# altimetrModul.net
KiCad netlist of a schematic drawn in EAGLE
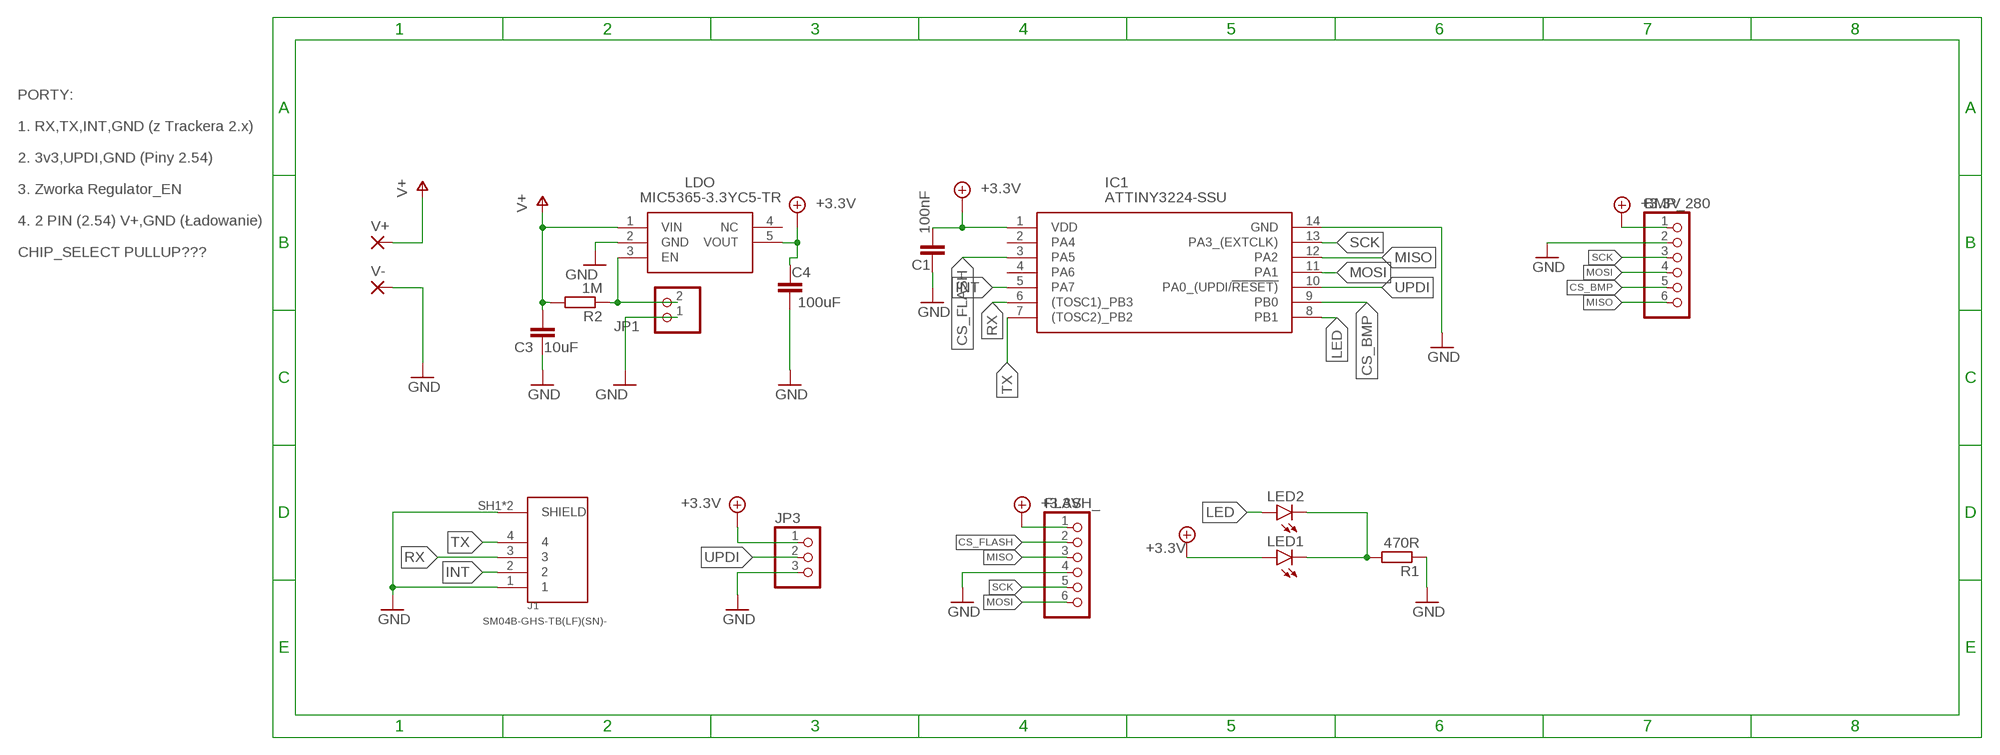
[diagram p0: schematic, sheet 1]

(export (version "E")
  (design (tool "Eeschema 10.0.6"))
  (components
    (comp (ref "BMP_280")
      (value "PINHD-1X6")
      (footprint "eagle-import:1X06")
      (libsource (lib "eagle-import") (part "PINHD-1X6"))
    )
    (comp (ref "C1")
      (value "100nF")
      (footprint "eagle-import:C0805")
      (libsource (lib "eagle-import") (part "C-EUC0805"))
    )
    (comp (ref "C3")
      (value "10uF")
      (footprint "eagle-import:C0805")
      (libsource (lib "eagle-import") (part "C-EUC0805"))
    )
    (comp (ref "C4")
      (value "100uF")
      (footprint "eagle-import:C0805")
      (libsource (lib "eagle-import") (part "C-EUC0805"))
    )
    (comp (ref "FLASH_")
      (value "PINHD-1X6")
      (footprint "eagle-import:1X06")
      (libsource (lib "eagle-import") (part "PINHD-1X6"))
    )
    (comp (ref "IC1")
      (value "ATTINY3224-SSU")
      (footprint "eagle-import:SOIC127P600X175-14N")
      (fields (field (name "MOUSER_PART_NUMBER") "579-ATTINY3224-SSU"))
      (libsource (lib "eagle-import") (part "ATTINY3224-SSU"))
    )
    (comp (ref "J1")
      (value "SM04B-GHS-TB(LF)(SN)-")
      (footprint "eagle-import:JST_SM04B-GHS-TB(LF)(SN)-")
      (fields (field (name "DIGI-KEY_PART_NUMBER") "455-1566-6-ND") (field (name "MF") "JST Sales"))
      (libsource (lib "eagle-import") (part "SM04B-GHS-TB(LF)(SN)-"))
    )
    (comp (ref "JP1")
      (value "PINHD-1X2/90")
      (footprint "eagle-import:1X02_90")
      (libsource (lib "eagle-import") (part "PINHD-1X2/90"))
    )
    (comp (ref "JP3")
      (value "PINHD-1X3/90")
      (footprint "eagle-import:1X03_90")
      (libsource (lib "eagle-import") (part "PINHD-1X3/90"))
    )
    (comp (ref "LDO")
      (value "MIC5365-3.3YC5-TR")
      (footprint "eagle-import:SOT65P210X110-5N")
      (fields (field (name "MOUSER_PART_NUMBER") "998-MIC5365-3.3YC5TR"))
      (libsource (lib "eagle-import") (part "MIC5365-3.3YC5-TR"))
    )
    (comp (ref "LED1")
      (value "LEDCHIP-LED0805")
      (footprint "eagle-import:CHIP-LED0805")
      (libsource (lib "eagle-import") (part "LEDCHIP-LED0805"))
    )
    (comp (ref "LED2")
      (value "LEDCHIP-LED0805")
      (footprint "eagle-import:CHIP-LED0805")
      (libsource (lib "eagle-import") (part "LEDCHIP-LED0805"))
    )
    (comp (ref "R1")
      (value "470R")
      (footprint "eagle-import:R0805")
      (libsource (lib "eagle-import") (part "rcl_334_R-EU_R0805"))
    )
    (comp (ref "R2")
      (value "1M")
      (footprint "eagle-import:R0805")
      (libsource (lib "eagle-import") (part "R-EU_R0805"))
    )
    (comp (ref "V+")
      (value "SMD2")
      (footprint "eagle-import:SMD1,27-2,54")
      (libsource (lib "eagle-import") (part "SMD2"))
    )
    (comp (ref "V-")
      (value "SMD2")
      (footprint "eagle-import:SMD1,27-2,54")
      (libsource (lib "eagle-import") (part "SMD2"))
    )
  )
  (nets
    (net (code "1") (name "+3.3V") (class "Default")
      (node (ref "BMP_280") (pin "1") (pinfunction "1_1") (pintype "passive"))
      (node (ref "C1") (pin "1") (pinfunction "1_1") (pintype "passive"))
      (node (ref "C4") (pin "2") (pinfunction "2_2") (pintype "passive"))
      (node (ref "FLASH_") (pin "1") (pinfunction "1_1") (pintype "passive"))
      (node (ref "IC1") (pin "1") (pinfunction "VDD_1") (pintype "bidirectional"))
      (node (ref "JP3") (pin "1") (pinfunction "1_1") (pintype "passive"))
      (node (ref "LDO") (pin "5") (pinfunction "VOUT_5") (pintype "output"))
      (node (ref "LED1") (pin "A") (pinfunction "A_A") (pintype "passive"))
    )
    (net (code "2") (name "CS_BMP") (class "Default")
      (node (ref "BMP_280") (pin "5") (pinfunction "5_5") (pintype "passive"))
      (node (ref "IC1") (pin "9") (pinfunction "PB0_9") (pintype "bidirectional"))
    )
    (net (code "3") (name "CS_FLASH") (class "Default")
      (node (ref "FLASH_") (pin "2") (pinfunction "2_2") (pintype "passive"))
      (node (ref "IC1") (pin "3") (pinfunction "PA5_3") (pintype "bidirectional"))
    )
    (net (code "4") (name "GND") (class "Default")
      (node (ref "BMP_280") (pin "2") (pinfunction "2_2") (pintype "passive"))
      (node (ref "C1") (pin "2") (pinfunction "2_2") (pintype "passive"))
      (node (ref "C3") (pin "1") (pinfunction "1_1") (pintype "passive"))
      (node (ref "C4") (pin "1") (pinfunction "1_1") (pintype "passive"))
      (node (ref "FLASH_") (pin "4") (pinfunction "4_4") (pintype "passive"))
      (node (ref "IC1") (pin "14") (pinfunction "GND_14") (pintype "bidirectional"))
      (node (ref "J1") (pin "1") (pinfunction "1_1") (pintype "passive"))
      (node (ref "J1") (pin "SH1") (pinfunction "SHIELD_SH1") (pintype "power_in"))
      (node (ref "J1") (pin "SH2") (pinfunction "SHIELD_SH2") (pintype "power_in"))
      (node (ref "JP1") (pin "1") (pinfunction "1_1") (pintype "passive"))
      (node (ref "JP3") (pin "3") (pinfunction "3_3") (pintype "passive"))
      (node (ref "LDO") (pin "2") (pinfunction "GND_2") (pintype "power_in"))
      (node (ref "R1") (pin "1") (pinfunction "1_1") (pintype "passive"))
      (node (ref "V-") (pin "1") (pinfunction "P_1") (pintype "passive"))
    )
    (net (code "5") (name "INT") (class "Default")
      (node (ref "IC1") (pin "5") (pinfunction "PA7_5") (pintype "bidirectional"))
      (node (ref "J1") (pin "2") (pinfunction "2_2") (pintype "passive"))
    )
    (net (code "6") (name "LED") (class "Default")
      (node (ref "IC1") (pin "8") (pinfunction "PB1_8") (pintype "bidirectional"))
      (node (ref "LED2") (pin "A") (pinfunction "A_A") (pintype "passive"))
    )
    (net (code "7") (name "MISO") (class "Default")
      (node (ref "BMP_280") (pin "6") (pinfunction "6_6") (pintype "passive"))
      (node (ref "FLASH_") (pin "3") (pinfunction "3_3") (pintype "passive"))
      (node (ref "IC1") (pin "12") (pinfunction "PA2_12") (pintype "bidirectional"))
    )
    (net (code "8") (name "MOSI") (class "Default")
      (node (ref "BMP_280") (pin "4") (pinfunction "4_4") (pintype "passive"))
      (node (ref "FLASH_") (pin "6") (pinfunction "6_6") (pintype "passive"))
      (node (ref "IC1") (pin "11") (pinfunction "PA1_11") (pintype "bidirectional"))
    )
    (net (code "9") (name "Net-(LDO-EN)") (class "Default")
      (node (ref "JP1") (pin "2") (pinfunction "2_2") (pintype "passive"))
      (node (ref "LDO") (pin "3") (pinfunction "EN_3") (pintype "input"))
      (node (ref "R2") (pin "1") (pinfunction "1_1") (pintype "passive"))
    )
    (net (code "10") (name "Net-(LED1-PadC)") (class "Default")
      (node (ref "LED1") (pin "C") (pinfunction "C_C") (pintype "passive"))
      (node (ref "LED2") (pin "C") (pinfunction "C_C") (pintype "passive"))
      (node (ref "R1") (pin "2") (pinfunction "2_2") (pintype "passive"))
    )
    (net (code "11") (name "RX") (class "Default")
      (node (ref "IC1") (pin "6") (pinfunction "(TOSC1)_PB3_6") (pintype "bidirectional"))
      (node (ref "J1") (pin "3") (pinfunction "3_3") (pintype "passive"))
    )
    (net (code "12") (name "SCK") (class "Default")
      (node (ref "BMP_280") (pin "3") (pinfunction "3_3") (pintype "passive"))
      (node (ref "FLASH_") (pin "5") (pinfunction "5_5") (pintype "passive"))
      (node (ref "IC1") (pin "13") (pinfunction "PA3_(EXTCLK)_13") (pintype "bidirectional"))
    )
    (net (code "13") (name "TX") (class "Default")
      (node (ref "IC1") (pin "7") (pinfunction "(TOSC2)_PB2_7") (pintype "bidirectional"))
      (node (ref "J1") (pin "4") (pinfunction "4_4") (pintype "passive"))
    )
    (net (code "14") (name "UPDI") (class "Default")
      (node (ref "IC1") (pin "10") (pinfunction "PA0_(UPDI/~{RESET})_10") (pintype "bidirectional"))
      (node (ref "JP3") (pin "2") (pinfunction "2_2") (pintype "passive"))
    )
    (net (code "15") (name "V+") (class "Default")
      (node (ref "C3") (pin "2") (pinfunction "2_2") (pintype "passive"))
      (node (ref "LDO") (pin "1") (pinfunction "VIN_1") (pintype "power_in"))
      (node (ref "R2") (pin "2") (pinfunction "2_2") (pintype "passive"))
      (node (ref "V+") (pin "1") (pinfunction "P_1") (pintype "passive"))
    )
    (net (code "16") (name "unconnected-(IC1-PA4-Pad2)") (class "Default")
      (node (ref "IC1") (pin "2") (pinfunction "PA4_2") (pintype "bidirectional"))
    )
    (net (code "17") (name "unconnected-(IC1-PA6-Pad4)") (class "Default")
      (node (ref "IC1") (pin "4") (pinfunction "PA6_4") (pintype "bidirectional"))
    )
    (net (code "18") (name "unconnected-(LDO-NC-Pad4)") (class "Default")
      (node (ref "LDO") (pin "4") (pinfunction "NC_4") (pintype "no_connect"))
    )
  )
)
